# power6.net
KiCad netlist of a schematic drawn in Altium Designer
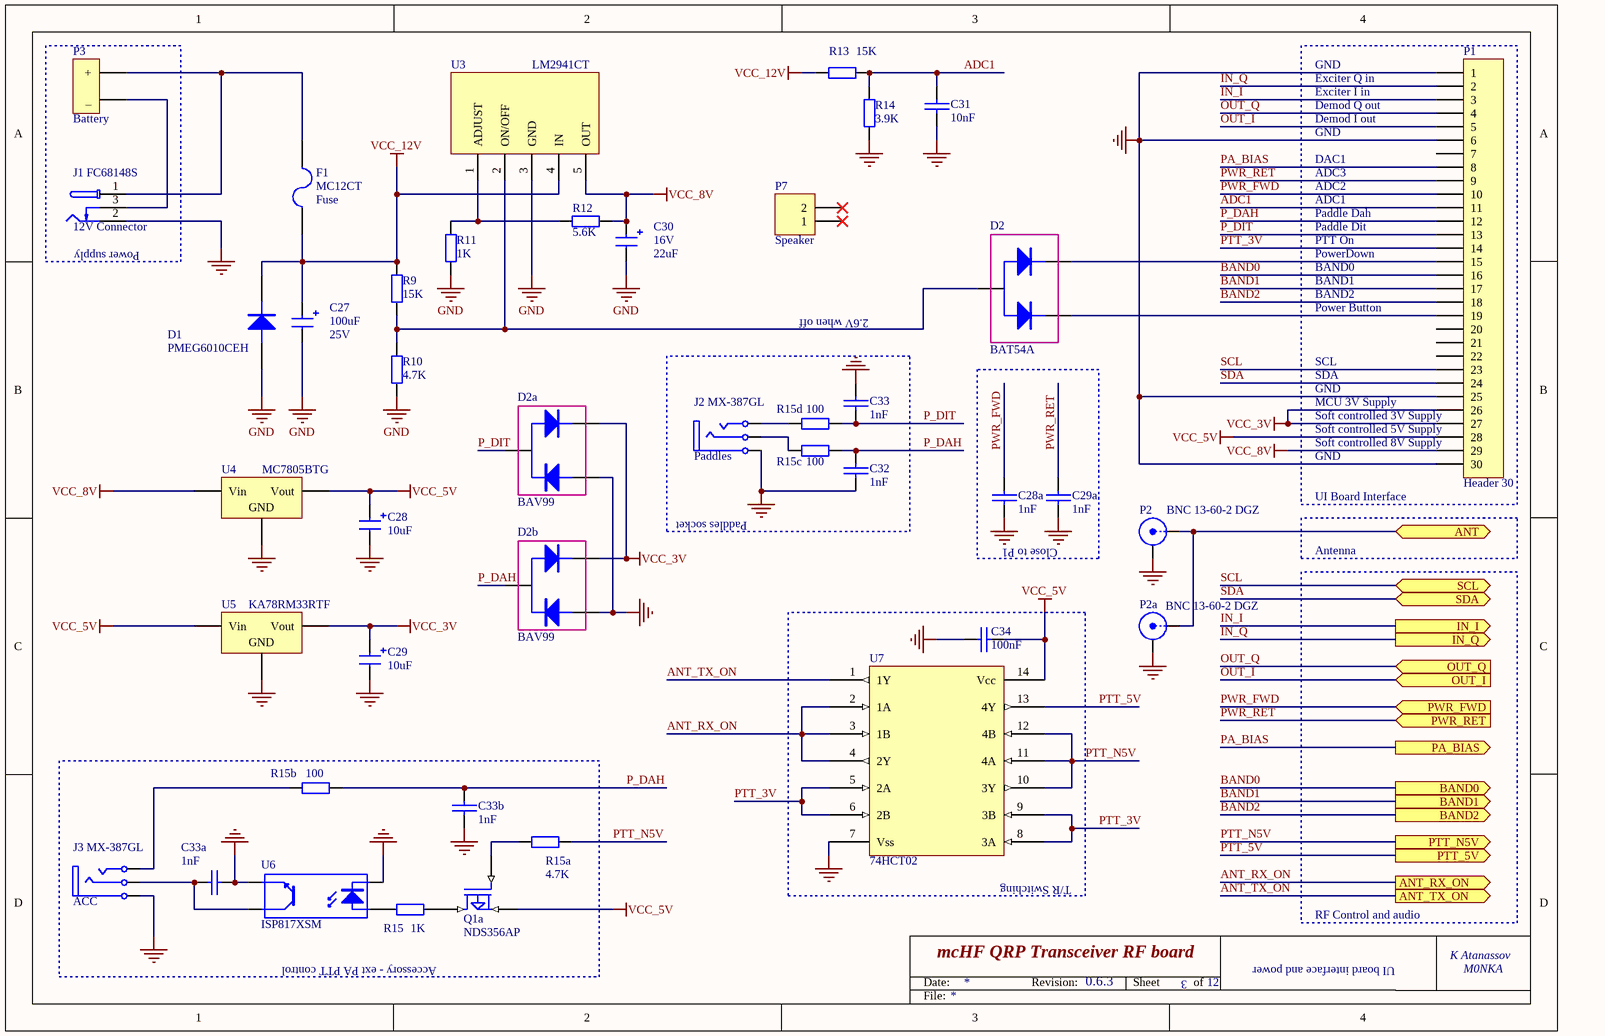
[diagram p0: power6.SchDoc]

(export (version "E")
  (design (tool "Eeschema 10.0.6"))
  (components
    (comp (ref "C27")
      (value "100uF")
      (footprint "CAP_ALUM_1")
      (description "Electrolitic capacitor")
      (fields (field (name "VOLTAGE") "25V"))
      (libsource (lib "mcHF_rf") (part "CAP-POL"))
    )
    (comp (ref "C28")
      (value "10uF")
      (footprint "1206_Elec_Cap_N")
      (description "Electrolitic capacitor")
      (libsource (lib "mcHF_rf") (part "CAP-POL"))
    )
    (comp (ref "C28a")
      (value "1nF")
      (footprint "0805-Pro")
      (description "Capacitor")
      (libsource (lib "mcHF_rf") (part "CAP"))
    )
    (comp (ref "C29")
      (value "10uF")
      (footprint "1206_Elec_Cap_N")
      (description "Electrolitic capacitor")
      (libsource (lib "mcHF_rf") (part "CAP-POL"))
    )
    (comp (ref "C29a")
      (value "1nF")
      (footprint "0805-Pro")
      (description "Capacitor")
      (libsource (lib "mcHF_rf") (part "CAP"))
    )
    (comp (ref "C30")
      (value "22uF")
      (footprint "1206_Elec_Cap_N")
      (description "Electrolitic capacitor")
      (fields (field (name "VOLTAGE") "16V"))
      (libsource (lib "mcHF_rf") (part "CAP-POL"))
    )
    (comp (ref "C31")
      (value "10nF")
      (footprint "0805-Pro")
      (description "Capacitor")
      (libsource (lib "mcHF_rf") (part "CAP"))
    )
    (comp (ref "C32")
      (value "1nF")
      (footprint "0805-Pro")
      (description "Capacitor")
      (libsource (lib "mcHF_rf") (part "CAP"))
    )
    (comp (ref "C33")
      (value "1nF")
      (footprint "0805-Pro")
      (description "Capacitor")
      (libsource (lib "mcHF_rf") (part "CAP"))
    )
    (comp (ref "C33a")
      (value "1nF")
      (footprint "0805-Pro")
      (description "Capacitor")
      (libsource (lib "mcHF_rf") (part "CAP"))
    )
    (comp (ref "C33b")
      (value "1nF")
      (footprint "0805-Pro")
      (description "Capacitor")
      (libsource (lib "mcHF_rf") (part "CAP"))
    )
    (comp (ref "C34")
      (value "100nF")
      (footprint "0805-Pro")
      (description "Capacitor")
      (libsource (lib "mcHF_rf") (part "CAP"))
    )
    (comp (ref "D1")
      (value "PMEG6010CEH")
      (footprint "SOD87")
      (description "DIODE, SCHOTTKY, 1A, 60V, SOD-123F")
      (libsource (lib "mcHF_rf") (part "PMEG6010CEH"))
    )
    (comp (ref "D2")
      (value "BAT54A")
      (footprint "SOT-23")
      (description "DIODE, SCHOTTKY, DUAL")
      (libsource (lib "mcHF_rf") (part "BAT54A"))
    )
    (comp (ref "D2a")
      (value "BAV99")
      (footprint "SOT-23")
      (description "Small Signal Diode, Dual Series")
      (libsource (lib "mcHF_rf") (part "BAV99"))
    )
    (comp (ref "D2b")
      (value "BAV99")
      (footprint "SOT-23")
      (description "Small Signal Diode, Dual Series")
      (libsource (lib "mcHF_rf") (part "BAV99"))
    )
    (comp (ref "F1")
      (value "MC12CT")
      (footprint "1206")
      (description "Fuse")
      (fields (field (name "FUNCTION") "Fuse"))
      (libsource (lib "mcHF_rf") (part "Fuse"))
    )
    (comp (ref "J1")
      (value "FC68148S")
      (footprint "PowerJack")
      (description "Power Jack")
      (fields (field (name "FUNCTION") "12V Connector"))
      (libsource (lib "mcHF_rf") (part "POWER_JACK"))
    )
    (comp (ref "J2")
      (value "MX-387GL")
      (footprint "MX-387GL_new1")
      (description "Jack Socket,Thru-Hole")
      (fields (field (name "FUNCTION") "Paddles"))
      (libsource (lib "mcHF_rf") (part "Phonejack3"))
    )
    (comp (ref "J3")
      (value "MX-387GL")
      (footprint "MX-387GL_new1")
      (description "Jack Socket,Thru-Hole")
      (fields (field (name "FUNCTION") "ACC"))
      (libsource (lib "mcHF_rf") (part "Phonejack3"))
    )
    (comp (ref "P1")
      (value "Header 30")
      (footprint "HDR1X30")
      (description "Header, 30-Pin")
      (libsource (lib "mcHF_rf") (part "Header 30"))
    )
    (comp (ref "P2")
      (value "BNC 13-60-2 DGZ")
      (footprint "CON-SMA-RA-A")
      (description "RF COAXIAL, BNC, JACK")
      (libsource (lib "mcHF_rf") (part "BNC"))
    )
    (comp (ref "P2a")
      (value "BNC 13-60-2 DGZ")
      (footprint "BNC_RA CON")
      (description "RF COAXIAL, BNC, JACK")
      (libsource (lib "mcHF_rf") (part "BNC"))
    )
    (comp (ref "P3")
      (value "Battery")
      (footprint "BatteryTerminal")
      (description "Battery Terminal")
      (libsource (lib "mcHF_rf") (part "Battery"))
    )
    (comp (ref "P7")
      (value "Speaker")
      (footprint "SIP2")
      (description "Header, 2-Pin")
      (fields (field (name "CHECKED") "NA"))
      (libsource (lib "mcHF_ui") (part "Header 2"))
    )
    (comp (ref "Q1a")
      (value "NDS356AP")
      (footprint "SOT-23-Pro")
      (libsource (lib "mcHF_rf") (part "NDS356AP"))
    )
    (comp (ref "R9")
      (value "15K")
      (footprint "0805-Pro")
      (description "Resistor")
      (libsource (lib "") (part "RES_2"))
    )
    (comp (ref "R10")
      (value "4.7K")
      (footprint "0805-Pro")
      (description "Resistor")
      (libsource (lib "mcHF_rf") (part "RES"))
    )
    (comp (ref "R11")
      (value "1K")
      (footprint "0805-Pro")
      (description "Resistor")
      (libsource (lib "") (part "RES_2"))
    )
    (comp (ref "R12")
      (value "5.6K")
      (footprint "0805-Pro")
      (description "Resistor")
      (libsource (lib "") (part "RES_1"))
    )
    (comp (ref "R13")
      (value "15K")
      (footprint "0805-Pro")
      (description "Resistor")
      (libsource (lib "") (part "RES_1"))
    )
    (comp (ref "R14")
      (value "3.9K")
      (footprint "0805-Pro")
      (description "Resistor")
      (libsource (lib "mcHF_rf") (part "RES"))
    )
    (comp (ref "R15")
      (value "1K")
      (footprint "0805-Pro")
      (description "Resistor")
      (libsource (lib "") (part "RES_1"))
    )
    (comp (ref "R15a")
      (value "4.7K")
      (footprint "0805-Pro")
      (description "Resistor")
      (libsource (lib "") (part "RES_1"))
    )
    (comp (ref "R15b")
      (value "100")
      (footprint "0805-Pro")
      (description "Resistor")
      (libsource (lib "*") (part "RES"))
    )
    (comp (ref "R15c")
      (value "100")
      (footprint "0805-Pro")
      (description "Resistor")
      (libsource (lib "*") (part "RES"))
    )
    (comp (ref "R15d")
      (value "100")
      (footprint "0805-Pro")
      (description "Resistor")
      (libsource (lib "*") (part "RES"))
    )
    (comp (ref "U3")
      (value "LM2941CT")
      (footprint "TO-220-5")
      (description "V REG ADJ +5/20V, 2941, TO-220-5")
      (libsource (lib "mcHF_rf") (part "LM2941CT"))
    )
    (comp (ref "U4")
      (value "MC7805BTG")
      (footprint "TO-220")
      (description "VOLTAGE REG, 40V, TO220-3")
      (libsource (lib "mcHF_rf") (part "MC7805BTG"))
    )
    (comp (ref "U5")
      (value "KA78RM33RTF")
      (footprint "TO-252")
      (description "VOLT REG, 3.3V, TO-252")
      (libsource (lib "mcHF_rf") (part "UA78M33CKVURG3"))
    )
    (comp (ref "U6")
      (value "ISP817XSM")
      (footprint "SMDIP-4_new1")
      (description "OPTOCOUPLER, SMDIP-4, TR O/P")
      (libsource (lib "mcHF_rf") (part "ISP817XSM"))
    )
    (comp (ref "U7")
      (value "74HCT02")
      (footprint "SO-14-Pro")
      (description "Quad 2-input NOR gate")
      (libsource (lib "mcHF_rf") (part "74HCT02"))
    )
  )
  (nets
    (net (code "1") (name "/ADC1") (class "Default")
      (node (ref "C31") (pin "1") (pinfunction "1_1") (pintype "passive"))
      (node (ref "P1") (pin "11") (pinfunction "11_11") (pintype "passive"))
      (node (ref "R13") (pin "2") (pinfunction "2_2") (pintype "passive"))
      (node (ref "R14") (pin "1") (pinfunction "1_1") (pintype "passive"))
    )
    (net (code "2") (name "/ANT") (class "Default")
      (node (ref "P2") (pin "1") (pinfunction "X_1") (pintype "passive"))
      (node (ref "P2a") (pin "1") (pinfunction "X_1") (pintype "passive"))
    )
    (net (code "3") (name "/ANT_RX_ON") (class "Default")
      (node (ref "U7") (pin "2") (pinfunction "1A_2") (pintype "input"))
      (node (ref "U7") (pin "3") (pinfunction "1B_3") (pintype "input"))
      (node (ref "U7") (pin "4") (pinfunction "2Y_4") (pintype "output"))
    )
    (net (code "4") (name "/ANT_TX_ON") (class "Default")
      (node (ref "U7") (pin "1") (pinfunction "1Y_1") (pintype "output"))
    )
    (net (code "5") (name "/BAND0") (class "Default")
      (node (ref "P1") (pin "16") (pinfunction "16_16") (pintype "passive"))
    )
    (net (code "6") (name "/BAND1") (class "Default")
      (node (ref "P1") (pin "17") (pinfunction "17_17") (pintype "passive"))
    )
    (net (code "7") (name "/BAND2") (class "Default")
      (node (ref "P1") (pin "18") (pinfunction "18_18") (pintype "passive"))
    )
    (net (code "8") (name "/IN_I") (class "Default")
      (node (ref "P1") (pin "3") (pinfunction "3_3") (pintype "passive"))
    )
    (net (code "9") (name "/IN_Q") (class "Default")
      (node (ref "P1") (pin "2") (pinfunction "2_2") (pintype "passive"))
    )
    (net (code "10") (name "/OUT_I") (class "Default")
      (node (ref "P1") (pin "5") (pinfunction "5_5") (pintype "passive"))
    )
    (net (code "11") (name "/OUT_Q") (class "Default")
      (node (ref "P1") (pin "4") (pinfunction "4_4") (pintype "passive"))
    )
    (net (code "12") (name "/PA_BIAS") (class "Default")
      (node (ref "P1") (pin "8") (pinfunction "8_8") (pintype "passive"))
    )
    (net (code "13") (name "/PTT_3V") (class "Default")
      (node (ref "P1") (pin "14") (pinfunction "14_14") (pintype "passive"))
      (node (ref "U7") (pin "5") (pinfunction "2A_5") (pintype "input"))
      (node (ref "U7") (pin "6") (pinfunction "2B_6") (pintype "input"))
      (node (ref "U7") (pin "8") (pinfunction "3A_8") (pintype "input"))
      (node (ref "U7") (pin "9") (pinfunction "3B_9") (pintype "input"))
    )
    (net (code "14") (name "/PTT_5V") (class "Default")
      (node (ref "U7") (pin "13") (pinfunction "4Y_13") (pintype "output"))
    )
    (net (code "15") (name "/PTT_N5V") (class "Default")
      (node (ref "R15a") (pin "2") (pinfunction "2_2") (pintype "passive"))
      (node (ref "U7") (pin "10") (pinfunction "3Y_10") (pintype "output"))
      (node (ref "U7") (pin "11") (pinfunction "4A_11") (pintype "input"))
      (node (ref "U7") (pin "12") (pinfunction "4B_12") (pintype "input"))
    )
    (net (code "16") (name "/PWR_FWD") (class "Default")
      (node (ref "C28a") (pin "2") (pinfunction "2_2") (pintype "passive"))
      (node (ref "P1") (pin "10") (pinfunction "10_10") (pintype "passive"))
    )
    (net (code "17") (name "/PWR_RET") (class "Default")
      (node (ref "C29a") (pin "2") (pinfunction "2_2") (pintype "passive"))
      (node (ref "P1") (pin "9") (pinfunction "9_9") (pintype "passive"))
    )
    (net (code "18") (name "/P_DAH") (class "Default")
      (node (ref "C32") (pin "2") (pinfunction "2_2") (pintype "passive"))
      (node (ref "C33b") (pin "1") (pinfunction "1_1") (pintype "passive"))
      (node (ref "D2b") (pin "3") (pinfunction "C_3") (pintype "passive"))
      (node (ref "P1") (pin "12") (pinfunction "12_12") (pintype "passive"))
      (node (ref "R15b") (pin "1") (pinfunction "1_1") (pintype "passive"))
      (node (ref "R15c") (pin "1") (pinfunction "1_1") (pintype "passive"))
    )
    (net (code "19") (name "/P_DIT") (class "Default")
      (node (ref "C33") (pin "1") (pinfunction "1_1") (pintype "passive"))
      (node (ref "D2a") (pin "3") (pinfunction "C_3") (pintype "passive"))
      (node (ref "P1") (pin "13") (pinfunction "13_13") (pintype "passive"))
      (node (ref "R15d") (pin "1") (pinfunction "1_1") (pintype "passive"))
    )
    (net (code "20") (name "/SCL") (class "Default")
      (node (ref "P1") (pin "23") (pinfunction "23_23") (pintype "passive"))
    )
    (net (code "21") (name "/SDA") (class "Default")
      (node (ref "P1") (pin "24") (pinfunction "24_24") (pintype "passive"))
    )
    (net (code "22") (name "GND") (class "Default")
      (node (ref "C27") (pin "2") (pinfunction "2_2") (pintype "passive"))
      (node (ref "C28") (pin "2") (pinfunction "2_2") (pintype "passive"))
      (node (ref "C28a") (pin "1") (pinfunction "1_1") (pintype "passive"))
      (node (ref "C29") (pin "2") (pinfunction "2_2") (pintype "passive"))
      (node (ref "C29a") (pin "1") (pinfunction "1_1") (pintype "passive"))
      (node (ref "C30") (pin "2") (pinfunction "2_2") (pintype "passive"))
      (node (ref "C31") (pin "2") (pinfunction "2_2") (pintype "passive"))
      (node (ref "C32") (pin "1") (pinfunction "1_1") (pintype "passive"))
      (node (ref "C33") (pin "2") (pinfunction "2_2") (pintype "passive"))
      (node (ref "C33a") (pin "1") (pinfunction "1_1") (pintype "passive"))
      (node (ref "C33b") (pin "2") (pinfunction "2_2") (pintype "passive"))
      (node (ref "C34") (pin "2") (pinfunction "2_2") (pintype "passive"))
      (node (ref "D1") (pin "1") (pinfunction "A_1") (pintype "passive"))
      (node (ref "D2a") (pin "1") (pinfunction "A1_1") (pintype "passive"))
      (node (ref "D2b") (pin "1") (pinfunction "A1_1") (pintype "passive"))
      (node (ref "J1") (pin "2") (pintype "passive"))
      (node (ref "J2") (pin "S") (pinfunction "S_S") (pintype "power_in"))
      (node (ref "J3") (pin "S") (pinfunction "S_S") (pintype "power_in"))
      (node (ref "P1") (pin "1") (pinfunction "1_1") (pintype "passive"))
      (node (ref "P1") (pin "25") (pinfunction "25_25") (pintype "passive"))
      (node (ref "P1") (pin "30") (pinfunction "30_30") (pintype "passive"))
      (node (ref "P1") (pin "6") (pinfunction "6_6") (pintype "passive"))
      (node (ref "P2") (pin "2") (pinfunction "Y_2") (pintype "passive"))
      (node (ref "P2a") (pin "2") (pinfunction "Y_2") (pintype "passive"))
      (node (ref "R10") (pin "2") (pinfunction "2_2") (pintype "passive"))
      (node (ref "R11") (pin "1") (pinfunction "1_1") (pintype "passive"))
      (node (ref "R14") (pin "2") (pinfunction "2_2") (pintype "passive"))
      (node (ref "U3") (pin "3") (pinfunction "GND_3") (pintype "passive"))
      (node (ref "U4") (pin "2") (pinfunction "GND_2") (pintype "passive"))
      (node (ref "U5") (pin "2") (pinfunction "GND_2") (pintype "passive"))
      (node (ref "U6") (pin "2") (pinfunction "K_2") (pintype "passive"))
      (node (ref "U6") (pin "3") (pinfunction "E_3") (pintype "passive"))
      (node (ref "U7") (pin "7") (pinfunction "Vss_7") (pintype "power_in"))
    )
    (net (code "23") (name "Net-(D2-A)") (class "Default")
      (node (ref "D2") (pin "3") (pinfunction "A_3") (pintype "passive"))
      (node (ref "R10") (pin "1") (pinfunction "1_1") (pintype "passive"))
      (node (ref "R9") (pin "1") (pinfunction "1_1") (pintype "passive"))
      (node (ref "U3") (pin "2") (pinfunction "ON/OFF_2") (pintype "passive"))
    )
    (net (code "24") (name "Net-(D2-K1)") (class "Default")
      (node (ref "D2") (pin "1") (pinfunction "K1_1") (pintype "passive"))
      (node (ref "P1") (pin "19") (pinfunction "19_19") (pintype "passive"))
    )
    (net (code "25") (name "Net-(D2-K2)") (class "Default")
      (node (ref "D2") (pin "2") (pinfunction "K2_2") (pintype "passive"))
      (node (ref "P1") (pin "15") (pinfunction "15_15") (pintype "passive"))
    )
    (net (code "26") (name "Net-(J2-PadR)") (class "Default")
      (node (ref "J2") (pin "R") (pinfunction "R_R") (pintype "passive"))
      (node (ref "R15c") (pin "2") (pinfunction "2_2") (pintype "passive"))
    )
    (net (code "27") (name "Net-(J2-PadT)") (class "Default")
      (node (ref "J2") (pin "T") (pinfunction "T_T") (pintype "passive"))
      (node (ref "R15d") (pin "2") (pinfunction "2_2") (pintype "passive"))
    )
    (net (code "28") (name "Net-(J3-PadT)") (class "Default")
      (node (ref "J3") (pin "T") (pinfunction "T_T") (pintype "passive"))
      (node (ref "R15b") (pin "2") (pinfunction "2_2") (pintype "passive"))
    )
    (net (code "29") (name "Net-(P3-+)") (class "Default")
      (node (ref "F1") (pin "2") (pinfunction "2_2") (pintype "passive"))
      (node (ref "J1") (pin "1") (pintype "passive"))
      (node (ref "P3") (pin "1") (pinfunction "+_1") (pintype "passive"))
    )
    (net (code "30") (name "Net-(P3-_)") (class "Default")
      (node (ref "J1") (pin "3") (pintype "passive"))
      (node (ref "P3") (pin "2") (pinfunction "__2") (pintype "passive"))
    )
    (net (code "31") (name "Net-(Q1a-D)") (class "Default")
      (node (ref "Q1a") (pin "3") (pinfunction "D_3") (pintype "input"))
      (node (ref "R15") (pin "2") (pinfunction "2_2") (pintype "passive"))
    )
    (net (code "32") (name "Net-(Q1a-G)") (class "Default")
      (node (ref "Q1a") (pin "1") (pinfunction "G_1") (pintype "input"))
      (node (ref "R15a") (pin "1") (pinfunction "1_1") (pintype "passive"))
    )
    (net (code "33") (name "Net-(U3-ADJUST)") (class "Default")
      (node (ref "R11") (pin "2") (pinfunction "2_2") (pintype "passive"))
      (node (ref "R12") (pin "1") (pinfunction "1_1") (pintype "passive"))
      (node (ref "U3") (pin "1") (pinfunction "ADJUST_1") (pintype "passive"))
    )
    (net (code "34") (name "Net-(U6-A)") (class "Default")
      (node (ref "R15") (pin "1") (pinfunction "1_1") (pintype "passive"))
      (node (ref "U6") (pin "1") (pinfunction "A_1") (pintype "passive"))
    )
    (net (code "35") (name "Net-(U6-C)") (class "Default")
      (node (ref "C33a") (pin "2") (pinfunction "2_2") (pintype "passive"))
      (node (ref "J3") (pin "R") (pinfunction "R_R") (pintype "passive"))
      (node (ref "U6") (pin "4") (pinfunction "C_4") (pintype "passive"))
    )
    (net (code "36") (name "VCC_3V") (class "Default")
      (node (ref "C29") (pin "1") (pinfunction "1_1") (pintype "passive"))
      (node (ref "D2a") (pin "2") (pinfunction "K1_2") (pintype "passive"))
      (node (ref "D2b") (pin "2") (pinfunction "K1_2") (pintype "passive"))
      (node (ref "P1") (pin "26") (pinfunction "26_26") (pintype "passive"))
      (node (ref "P1") (pin "27") (pinfunction "27_27") (pintype "passive"))
      (node (ref "U5") (pin "3") (pinfunction "Vout_3") (pintype "passive"))
    )
    (net (code "37") (name "VCC_5V") (class "Default")
      (node (ref "C28") (pin "1") (pinfunction "1_1") (pintype "passive"))
      (node (ref "C34") (pin "1") (pinfunction "1_1") (pintype "passive"))
      (node (ref "P1") (pin "28") (pinfunction "28_28") (pintype "passive"))
      (node (ref "Q1a") (pin "2") (pinfunction "S_2") (pintype "input"))
      (node (ref "U4") (pin "3") (pinfunction "Vout_3") (pintype "passive"))
      (node (ref "U5") (pin "1") (pinfunction "Vin_1") (pintype "passive"))
      (node (ref "U7") (pin "14") (pinfunction "Vcc_14") (pintype "power_in"))
    )
    (net (code "38") (name "VCC_8V") (class "Default")
      (node (ref "C30") (pin "1") (pinfunction "1_1") (pintype "passive"))
      (node (ref "P1") (pin "29") (pinfunction "29_29") (pintype "passive"))
      (node (ref "R12") (pin "2") (pinfunction "2_2") (pintype "passive"))
      (node (ref "U3") (pin "5") (pinfunction "OUT_5") (pintype "passive"))
      (node (ref "U4") (pin "1") (pinfunction "Vin_1") (pintype "passive"))
    )
    (net (code "39") (name "VCC_12V") (class "Default")
      (node (ref "C27") (pin "1") (pinfunction "1_1") (pintype "passive"))
      (node (ref "D1") (pin "2") (pinfunction "K_2") (pintype "passive"))
      (node (ref "F1") (pin "1") (pinfunction "1_1") (pintype "passive"))
      (node (ref "R13") (pin "1") (pinfunction "1_1") (pintype "passive"))
      (node (ref "R9") (pin "2") (pinfunction "2_2") (pintype "passive"))
      (node (ref "U3") (pin "4") (pinfunction "IN_4") (pintype "passive"))
    )
    (net (code "40") (name "unconnected-(P1-Pad7)") (class "Default")
      (node (ref "P1") (pin "7") (pinfunction "7_7") (pintype "passive"))
    )
    (net (code "41") (name "unconnected-(P1-Pad20)") (class "Default")
      (node (ref "P1") (pin "20") (pinfunction "20_20") (pintype "passive"))
    )
    (net (code "42") (name "unconnected-(P1-Pad21)") (class "Default")
      (node (ref "P1") (pin "21") (pinfunction "21_21") (pintype "passive"))
    )
    (net (code "43") (name "unconnected-(P1-Pad22)") (class "Default")
      (node (ref "P1") (pin "22") (pinfunction "22_22") (pintype "passive"))
    )
    (net (code "44") (name "unconnected-(P7-Pad1)") (class "Default")
      (node (ref "P7") (pin "1") (pinfunction "1_1") (pintype "passive+no_connect"))
    )
    (net (code "45") (name "unconnected-(P7-Pad2)") (class "Default")
      (node (ref "P7") (pin "2") (pinfunction "2_2") (pintype "passive+no_connect"))
    )
  )
)
